# power.net
KiCad netlist of a schematic drawn in Altium Designer
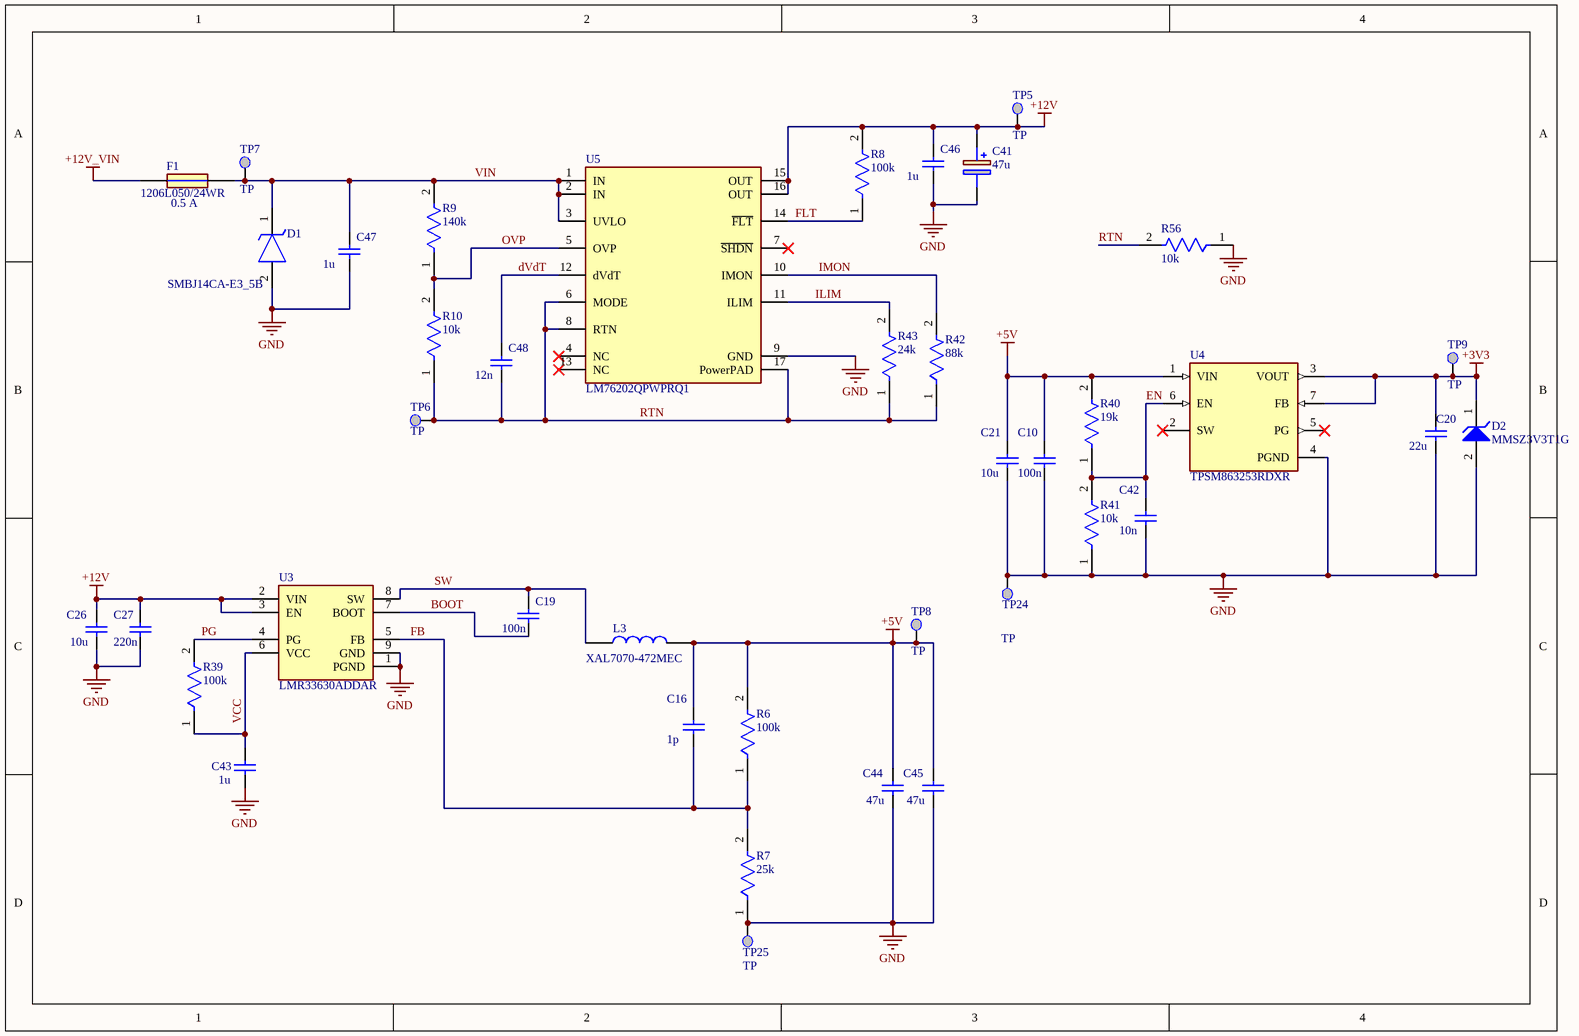
[diagram p0: power.SchDoc]

(export (version "E")
  (design (tool "Eeschema 10.0.6"))
  (components
    (comp (ref "C10")
      (value "100n")
      (footprint "CAPC1206(3216)150_L")
      (description "CAP 1.8uF 10V ±5% 1206 (3216 Metric) Thickness 1.45mm SMD")
      (fields (field (name "TOLERANCE") "Â±5%"))
      (libsource (lib "Altium Content Vault") (part "CAP"))
    )
    (comp (ref "C16")
      (value "1p")
      (footprint "CAPC1206(3216)150_L")
      (description "CAP 1.8uF 10V ±5% 1206 (3216 Metric) Thickness 1.45mm SMD")
      (fields (field (name "TOLERANCE") "Â±5%"))
      (libsource (lib "Altium Content Vault") (part "CAP"))
    )
    (comp (ref "C19")
      (value "100n")
      (footprint "CAPC1206(3216)150_L")
      (description "CAP 1.8uF 10V ±5% 1206 (3216 Metric) Thickness 1.45mm SMD")
      (fields (field (name "TOLERANCE") "Â±5%"))
      (libsource (lib "Altium Content Vault") (part "CAP"))
    )
    (comp (ref "C20")
      (value "22u")
      (footprint "CAPC1206(3216)150_L")
      (description "CAP 1.8uF 10V ±5% 1206 (3216 Metric) Thickness 1.45mm SMD")
      (fields (field (name "TOLERANCE") "Â±5%"))
      (libsource (lib "Altium Content Vault") (part "CAP"))
    )
    (comp (ref "C21")
      (value "10u")
      (footprint "CAPC1206(3216)150_L")
      (description "CAP 1.8uF 10V ±5% 1206 (3216 Metric) Thickness 1.45mm SMD")
      (fields (field (name "TOLERANCE") "Â±5%"))
      (libsource (lib "Altium Content Vault") (part "CAP"))
    )
    (comp (ref "C26")
      (value "10u")
      (footprint "CAPC1206(3216)150_L")
      (description "CAP 1.8uF 10V ±5% 1206 (3216 Metric) Thickness 1.45mm SMD")
      (fields (field (name "TOLERANCE") "Â±5%"))
      (libsource (lib "Altium Content Vault") (part "CAP"))
    )
    (comp (ref "C27")
      (value "220n")
      (footprint "CAPC1206(3216)150_L")
      (description "CAP 1.8uF 10V ±5% 1206 (3216 Metric) Thickness 1.45mm SMD")
      (fields (field (name "TOLERANCE") "Â±5%"))
      (libsource (lib "Altium Content Vault") (part "CAP"))
    )
    (comp (ref "C41")
      (value "47u")
      (footprint "EDK476M035S9GAA")
      (description "Surface Mount, Aluminum Electrolytic")
      (fields
        (field (name "MANUFACTURER_PART_NUMBER") "EDK476M035S9GAA")
        (field (name "MOUSER PART NUMBER") "80-EDK476M035S9GAA")
      )
      (libsource (lib "HydrogreenLibrary") (part "EDK476M035S9GAA"))
    )
    (comp (ref "C42")
      (value "10n")
      (footprint "CAPC1206(3216)150_L")
      (description "CAP 1.8uF 10V ±5% 1206 (3216 Metric) Thickness 1.45mm SMD")
      (fields (field (name "TOLERANCE") "Â±5%"))
      (libsource (lib "Altium Content Vault") (part "CAP"))
    )
    (comp (ref "C43")
      (value "1u")
      (footprint "CAPC1206(3216)150_L")
      (description "CAP 1.8uF 10V ±5% 1206 (3216 Metric) Thickness 1.45mm SMD")
      (fields (field (name "TOLERANCE") "Â±5%"))
      (libsource (lib "Altium Content Vault") (part "CAP"))
    )
    (comp (ref "C44")
      (value "47u")
      (footprint "CAPC1206(3216)150_L")
      (description "CAP 1.8uF 10V ±5% 1206 (3216 Metric) Thickness 1.45mm SMD")
      (fields (field (name "TOLERANCE") "Â±5%"))
      (libsource (lib "Altium Content Vault") (part "CAP"))
    )
    (comp (ref "C45")
      (value "47u")
      (footprint "CAPC1206(3216)150_L")
      (description "CAP 1.8uF 10V ±5% 1206 (3216 Metric) Thickness 1.45mm SMD")
      (fields (field (name "TOLERANCE") "Â±5%"))
      (libsource (lib "Altium Content Vault") (part "CAP"))
    )
    (comp (ref "C46")
      (value "1u")
      (footprint "CAPC1206(3216)150_L")
      (description "CAP 1.8uF 10V ±5% 1206 (3216 Metric) Thickness 1.45mm SMD")
      (fields (field (name "TOLERANCE") "Â±5%"))
      (libsource (lib "Altium Content Vault") (part "CAP"))
    )
    (comp (ref "C47")
      (value "1u")
      (footprint "CAPC1206(3216)150_L")
      (description "CAP 1.8uF 10V ±5% 1206 (3216 Metric) Thickness 1.45mm SMD")
      (fields (field (name "TOLERANCE") "Â±5%"))
      (libsource (lib "Altium Content Vault") (part "CAP"))
    )
    (comp (ref "C48")
      (value "12n")
      (footprint "CAPC1206(3216)150_L")
      (description "CAP 1.8uF 10V ±5% 1206 (3216 Metric) Thickness 1.45mm SMD")
      (fields (field (name "TOLERANCE") "Â±5%"))
      (libsource (lib "Altium Content Vault") (part "CAP"))
    )
    (comp (ref "D1")
      (value "SMBJ14CA-E3_5B")
      (footprint "SMBJ13A-E3_5B")
      (description "TVS Diode (Uni-directional)")
      (fields
        (field (name "MANUFACTURER_PART_NUMBER") "SMBJ13A-E3/5B")
        (field (name "MOUSER PART NUMBER") "625-SMBJ13A-E3/5B")
      )
      (libsource (lib "HydrogreenLibrary") (part "SMBJ13A-E3_5B"))
    )
    (comp (ref "D2")
      (value "MMSZ3V3T1G")
      (footprint "ONSC-SOD-123-2-425-04_V")
      (description "Zener Voltage Regulator, 500 mW, 2-Pin SOD-123, Pb-Free, Tape and Reel")
      (fields (field (name "MANUFACTURER") "On Semiconductor"))
      (libsource (lib "Altium Content Vault") (part "ONSC-K1A2-2"))
    )
    (comp (ref "F1")
      (value "1206L050/24WR")
      (footprint "0ZCJ0025FF2E")
      (description "BEL FUSE - CIRCUIT PROTECTION - 0ZCJ0025FF2E - FUSE, RESETTABLE PTC, 16VDC, 0.25A, SMD")
      (fields (field (name "MANUFACTURER_PART_NUMBER") "0ZCJ0025FF2E"))
      (libsource (lib "HydrogreenLibrary") (part "0ZCJ0025FF2E"))
    )
    (comp (ref "L3")
      (value "XAL7070-472MEC")
      (footprint "XAL7070472MEC")
      (description "General Purpose Inductor, 4.7uH, 20%, 1 Element, Composite-Core, SMD, 3028")
      (fields
        (field (name "MOUSER PART NUMBER") "994-XAL7070-472MEC")
        (field (name "MANUFACTURER") "Coilcraft")
      )
      (libsource (lib "HydrogreenLibrary") (part "XAL7070-472MEC"))
    )
    (comp (ref "R6")
      (value "100k")
      (footprint "FP-RK73H2B-MFG")
      (description "40.2kΩ ±1% 0.25W Chip Resistor 1206 Thick Film AEC-Q200 Qualified")
      (fields (field (name "TOLERANCE") "1%"))
      (libsource (lib "Altium Content Vault") (part "1029c3af85768c4190bb7ad29bc67b5"))
    )
    (comp (ref "R7")
      (value "25k")
      (footprint "FP-RK73H2B-MFG")
      (description "40.2kΩ ±1% 0.25W Chip Resistor 1206 Thick Film AEC-Q200 Qualified")
      (fields (field (name "TOLERANCE") "1%"))
      (libsource (lib "Altium Content Vault") (part "1029c3af85768c4190bb7ad29bc67b5"))
    )
    (comp (ref "R8")
      (value "100k")
      (footprint "FP-RK73H2B-MFG")
      (description "40.2kΩ ±1% 0.25W Chip Resistor 1206 Thick Film AEC-Q200 Qualified")
      (fields (field (name "TOLERANCE") "1%"))
      (libsource (lib "Altium Content Vault") (part "1029c3af85768c4190bb7ad29bc67b5"))
    )
    (comp (ref "R9")
      (value "140k")
      (footprint "FP-RK73H2B-MFG")
      (description "40.2kΩ ±1% 0.25W Chip Resistor 1206 Thick Film AEC-Q200 Qualified")
      (fields (field (name "TOLERANCE") "1%"))
      (libsource (lib "Altium Content Vault") (part "1029c3af85768c4190bb7ad29bc67b5"))
    )
    (comp (ref "R10")
      (value "10k")
      (footprint "FP-RK73H2B-MFG")
      (description "40.2kΩ ±1% 0.25W Chip Resistor 1206 Thick Film AEC-Q200 Qualified")
      (fields (field (name "TOLERANCE") "1%"))
      (libsource (lib "Altium Content Vault") (part "1029c3af85768c4190bb7ad29bc67b5"))
    )
    (comp (ref "R39")
      (value "100k")
      (footprint "FP-RK73H2B-MFG")
      (description "40.2kΩ ±1% 0.25W Chip Resistor 1206 Thick Film AEC-Q200 Qualified")
      (fields (field (name "TOLERANCE") "1%"))
      (libsource (lib "Altium Content Vault") (part "1029c3af85768c4190bb7ad29bc67b5"))
    )
    (comp (ref "R40")
      (value "19k")
      (footprint "FP-RK73H2B-MFG")
      (description "40.2kΩ ±1% 0.25W Chip Resistor 1206 Thick Film AEC-Q200 Qualified")
      (fields (field (name "TOLERANCE") "1%"))
      (libsource (lib "Altium Content Vault") (part "1029c3af85768c4190bb7ad29bc67b5"))
    )
    (comp (ref "R41")
      (value "10k")
      (footprint "FP-RK73H2B-MFG")
      (description "40.2kΩ ±1% 0.25W Chip Resistor 1206 Thick Film AEC-Q200 Qualified")
      (fields (field (name "TOLERANCE") "1%"))
      (libsource (lib "Altium Content Vault") (part "1029c3af85768c4190bb7ad29bc67b5"))
    )
    (comp (ref "R42")
      (value "88k")
      (footprint "FP-RK73H2B-MFG")
      (description "40.2kΩ ±1% 0.25W Chip Resistor 1206 Thick Film AEC-Q200 Qualified")
      (fields (field (name "TOLERANCE") "1%"))
      (libsource (lib "Altium Content Vault") (part "1029c3af85768c4190bb7ad29bc67b5"))
    )
    (comp (ref "R43")
      (value "24k")
      (footprint "FP-RK73H2B-MFG")
      (description "40.2kΩ ±1% 0.25W Chip Resistor 1206 Thick Film AEC-Q200 Qualified")
      (fields (field (name "TOLERANCE") "1%"))
      (libsource (lib "Altium Content Vault") (part "1029c3af85768c4190bb7ad29bc67b5"))
    )
    (comp (ref "R56")
      (value "10k")
      (footprint "FP-RK73H2B-MFG")
      (description "40.2kΩ ±1% 0.25W Chip Resistor 1206 Thick Film AEC-Q200 Qualified")
      (fields (field (name "TOLERANCE") "1%"))
      (libsource (lib "Altium Content Vault") (part "1029c3af85768c4190bb7ad29bc67b5"))
    )
    (comp (ref "TP5")
      (value "TP")
      (footprint "Test_Point")
      (libsource (lib "HydrogreenLibrary") (part "TestPoint"))
    )
    (comp (ref "TP6")
      (value "TP")
      (footprint "Test_Point")
      (libsource (lib "HydrogreenLibrary") (part "TestPoint"))
    )
    (comp (ref "TP7")
      (value "TP")
      (footprint "Test_Point")
      (libsource (lib "HydrogreenLibrary") (part "TestPoint"))
    )
    (comp (ref "TP8")
      (value "TP")
      (footprint "Test_Point")
      (libsource (lib "HydrogreenLibrary") (part "TestPoint"))
    )
    (comp (ref "TP9")
      (value "TP")
      (footprint "Test_Point")
      (libsource (lib "HydrogreenLibrary") (part "TestPoint"))
    )
    (comp (ref "TP24")
      (value "TP")
      (footprint "Test_Point")
      (libsource (lib "HydrogreenLibrary") (part "TestPoint"))
    )
    (comp (ref "TP25")
      (value "TP")
      (footprint "Test_Point")
      (libsource (lib "HydrogreenLibrary") (part "TestPoint"))
    )
    (comp (ref "U3")
      (value "LMR33630ADDAR")
      (footprint "LMR33630ADDAR")
      (fields
        (field (name "MOUSER PART NUMBER") "595-LMR33630ADDAR")
        (field (name "MANUFACTURER") "Texas Instruments")
      )
      (libsource (lib "HydrogreenLibrary") (part "LMR33630ADDAR"))
    )
    (comp (ref "U4")
      (value "TPSM863253RDXR")
      (footprint "TPSM863253RDXR")
      (fields (field (name "MF") "Texas Instruments"))
      (libsource (lib "HydrogreenLibrary") (part "TPSM863253RDXR"))
    )
    (comp (ref "U5")
      (value "LM76202QPWPRQ1")
      (footprint "FP-PWP0016H-MFG")
      (description "IC POWER MANAGEMENT")
      (libsource (lib "Altium Content Vault") (part "63852a48b58549ed9319a80900c418e"))
    )
  )
  (nets
    (net (code "1") (name "+3V3") (class "Default")
      (node (ref "C20") (pin "1") (pinfunction "1_1") (pintype "passive"))
      (node (ref "D2") (pin "1") (pinfunction "K_1") (pintype "passive"))
      (node (ref "TP9") (pin "1") (pinfunction "1_1") (pintype "passive"))
      (node (ref "U4") (pin "3") (pinfunction "VOUT_3") (pintype "output"))
      (node (ref "U4") (pin "7") (pinfunction "FB_7") (pintype "input"))
    )
    (net (code "2") (name "+5V") (class "Default")
      (node (ref "C10") (pin "1") (pinfunction "1_1") (pintype "passive"))
      (node (ref "C16") (pin "1") (pinfunction "1_1") (pintype "passive"))
      (node (ref "C21") (pin "1") (pinfunction "1_1") (pintype "passive"))
      (node (ref "C44") (pin "1") (pinfunction "1_1") (pintype "passive"))
      (node (ref "C45") (pin "1") (pinfunction "1_1") (pintype "passive"))
      (node (ref "L3") (pin "2") (pinfunction "2_2") (pintype "passive"))
      (node (ref "R40") (pin "2") (pinfunction "2_2") (pintype "passive"))
      (node (ref "R6") (pin "2") (pinfunction "2_2") (pintype "passive"))
      (node (ref "TP8") (pin "1") (pinfunction "1_1") (pintype "passive"))
      (node (ref "U4") (pin "1") (pinfunction "VIN_1") (pintype "input"))
    )
    (net (code "3") (name "+12V") (class "Default")
      (node (ref "C26") (pin "1") (pinfunction "1_1") (pintype "passive"))
      (node (ref "C27") (pin "1") (pinfunction "1_1") (pintype "passive"))
      (node (ref "C41") (pin "1") (pinfunction "+_1") (pintype "passive"))
      (node (ref "C46") (pin "1") (pinfunction "1_1") (pintype "passive"))
      (node (ref "R8") (pin "2") (pinfunction "2_2") (pintype "passive"))
      (node (ref "TP5") (pin "1") (pinfunction "1_1") (pintype "passive"))
      (node (ref "U3") (pin "2") (pinfunction "VIN_2") (pintype "passive"))
      (node (ref "U3") (pin "3") (pinfunction "EN_3") (pintype "passive"))
      (node (ref "U5") (pin "15") (pinfunction "OUT_15") (pintype "power_in"))
      (node (ref "U5") (pin "16") (pinfunction "OUT_16") (pintype "power_in"))
    )
    (net (code "4") (name "+12V_VIN") (class "Default")
      (node (ref "F1") (pin "1") (pinfunction "1_1") (pintype "passive"))
    )
    (net (code "5") (name "/BOOT") (class "Default")
      (node (ref "C19") (pin "2") (pinfunction "2_2") (pintype "passive"))
      (node (ref "U3") (pin "7") (pinfunction "BOOT_7") (pintype "passive"))
    )
    (net (code "6") (name "/EN") (class "Default")
      (node (ref "C42") (pin "1") (pinfunction "1_1") (pintype "passive"))
      (node (ref "R40") (pin "1") (pinfunction "1_1") (pintype "passive"))
      (node (ref "R41") (pin "2") (pinfunction "2_2") (pintype "passive"))
      (node (ref "U4") (pin "6") (pinfunction "EN_6") (pintype "input"))
    )
    (net (code "7") (name "/FB") (class "Default")
      (node (ref "C16") (pin "2") (pinfunction "2_2") (pintype "passive"))
      (node (ref "R6") (pin "1") (pinfunction "1_1") (pintype "passive"))
      (node (ref "R7") (pin "2") (pinfunction "2_2") (pintype "passive"))
      (node (ref "U3") (pin "5") (pinfunction "FB_5") (pintype "passive"))
    )
    (net (code "8") (name "/FLT") (class "Default")
      (node (ref "R8") (pin "1") (pinfunction "1_1") (pintype "passive"))
      (node (ref "U5") (pin "14") (pinfunction "~{FLT}_14") (pintype "passive"))
    )
    (net (code "9") (name "/ILIM") (class "Default")
      (node (ref "R43") (pin "2") (pinfunction "2_2") (pintype "passive"))
      (node (ref "U5") (pin "11") (pinfunction "ILIM_11") (pintype "passive"))
    )
    (net (code "10") (name "/IMON") (class "Default")
      (node (ref "R42") (pin "2") (pinfunction "2_2") (pintype "passive"))
      (node (ref "U5") (pin "10") (pinfunction "IMON_10") (pintype "passive"))
    )
    (net (code "11") (name "/OVP") (class "Default")
      (node (ref "R10") (pin "2") (pinfunction "2_2") (pintype "passive"))
      (node (ref "R9") (pin "1") (pinfunction "1_1") (pintype "passive"))
      (node (ref "U5") (pin "5") (pinfunction "OVP_5") (pintype "passive"))
    )
    (net (code "12") (name "/PG") (class "Default")
      (node (ref "R39") (pin "2") (pinfunction "2_2") (pintype "passive"))
      (node (ref "U3") (pin "4") (pinfunction "PG_4") (pintype "passive"))
    )
    (net (code "13") (name "/RTN") (class "Default")
      (node (ref "C48") (pin "2") (pinfunction "2_2") (pintype "passive"))
      (node (ref "R10") (pin "1") (pinfunction "1_1") (pintype "passive"))
      (node (ref "R42") (pin "1") (pinfunction "1_1") (pintype "passive"))
      (node (ref "R43") (pin "1") (pinfunction "1_1") (pintype "passive"))
      (node (ref "R56") (pin "2") (pinfunction "2_2") (pintype "passive"))
      (node (ref "TP6") (pin "1") (pinfunction "1_1") (pintype "passive"))
      (node (ref "U5") (pin "17") (pinfunction "PowerPAD_17") (pintype "power_in"))
      (node (ref "U5") (pin "6") (pinfunction "MODE_6") (pintype "passive"))
      (node (ref "U5") (pin "8") (pinfunction "RTN_8") (pintype "passive"))
    )
    (net (code "14") (name "/SW") (class "Default")
      (node (ref "C19") (pin "1") (pinfunction "1_1") (pintype "passive"))
      (node (ref "L3") (pin "1") (pinfunction "1_1") (pintype "passive"))
      (node (ref "U3") (pin "8") (pinfunction "SW_8") (pintype "passive"))
    )
    (net (code "15") (name "/VCC") (class "Default")
      (node (ref "C43") (pin "1") (pinfunction "1_1") (pintype "passive"))
      (node (ref "R39") (pin "1") (pinfunction "1_1") (pintype "passive"))
      (node (ref "U3") (pin "6") (pinfunction "VCC_6") (pintype "passive"))
    )
    (net (code "16") (name "/VIN") (class "Default")
      (node (ref "C47") (pin "1") (pinfunction "1_1") (pintype "passive"))
      (node (ref "D1") (pin "1") (pinfunction "K_1") (pintype "passive"))
      (node (ref "F1") (pin "2") (pinfunction "2_2") (pintype "passive"))
      (node (ref "R9") (pin "2") (pinfunction "2_2") (pintype "passive"))
      (node (ref "TP7") (pin "1") (pinfunction "1_1") (pintype "passive"))
      (node (ref "U5") (pin "1") (pinfunction "IN_1") (pintype "power_in"))
      (node (ref "U5") (pin "2") (pinfunction "IN_2") (pintype "power_in"))
      (node (ref "U5") (pin "3") (pinfunction "UVLO_3") (pintype "power_in"))
    )
    (net (code "17") (name "/dVdT") (class "Default")
      (node (ref "C48") (pin "1") (pinfunction "1_1") (pintype "passive"))
      (node (ref "U5") (pin "12") (pinfunction "dVdT_12") (pintype "passive"))
    )
    (net (code "18") (name "GND") (class "Default")
      (node (ref "C10") (pin "2") (pinfunction "2_2") (pintype "passive"))
      (node (ref "C20") (pin "2") (pinfunction "2_2") (pintype "passive"))
      (node (ref "C21") (pin "2") (pinfunction "2_2") (pintype "passive"))
      (node (ref "C26") (pin "2") (pinfunction "2_2") (pintype "passive"))
      (node (ref "C27") (pin "2") (pinfunction "2_2") (pintype "passive"))
      (node (ref "C41") (pin "2") (pinfunction "-_2") (pintype "passive"))
      (node (ref "C42") (pin "2") (pinfunction "2_2") (pintype "passive"))
      (node (ref "C43") (pin "2") (pinfunction "2_2") (pintype "passive"))
      (node (ref "C44") (pin "2") (pinfunction "2_2") (pintype "passive"))
      (node (ref "C45") (pin "2") (pinfunction "2_2") (pintype "passive"))
      (node (ref "C46") (pin "2") (pinfunction "2_2") (pintype "passive"))
      (node (ref "C47") (pin "2") (pinfunction "2_2") (pintype "passive"))
      (node (ref "D1") (pin "2") (pinfunction "A_2") (pintype "passive"))
      (node (ref "D2") (pin "2") (pinfunction "A_2") (pintype "passive"))
      (node (ref "R41") (pin "1") (pinfunction "1_1") (pintype "passive"))
      (node (ref "R56") (pin "1") (pinfunction "1_1") (pintype "passive"))
      (node (ref "R7") (pin "1") (pinfunction "1_1") (pintype "passive"))
      (node (ref "TP24") (pin "1") (pinfunction "1_1") (pintype "passive"))
      (node (ref "TP25") (pin "1") (pinfunction "1_1") (pintype "passive"))
      (node (ref "U3") (pin "1") (pinfunction "PGND_1") (pintype "passive"))
      (node (ref "U3") (pin "9") (pinfunction "GND_9") (pintype "passive"))
      (node (ref "U4") (pin "4") (pinfunction "PGND_4") (pintype "power_in"))
      (node (ref "U5") (pin "9") (pinfunction "GND_9") (pintype "power_in"))
    )
    (net (code "19") (name "unconnected-(U4-PG-Pad5)") (class "Default")
      (node (ref "U4") (pin "5") (pinfunction "PG_5") (pintype "output+no_connect"))
    )
    (net (code "20") (name "unconnected-(U4-SW-Pad2)") (class "Default")
      (node (ref "U4") (pin "2") (pinfunction "SW_2") (pintype "passive+no_connect"))
    )
    (net (code "21") (name "unconnected-(U5-NC-Pad4)") (class "Default")
      (node (ref "U5") (pin "4") (pinfunction "NC_4") (pintype "passive+no_connect"))
    )
    (net (code "22") (name "unconnected-(U5-NC-Pad13)") (class "Default")
      (node (ref "U5") (pin "13") (pinfunction "NC_13") (pintype "passive+no_connect"))
    )
    (net (code "23") (name "unconnected-(U5-~{SHDN}-Pad7)") (class "Default")
      (node (ref "U5") (pin "7") (pinfunction "~{SHDN}_7") (pintype "passive+no_connect"))
    )
  )
)
